# 7seg.net
KiCad netlist of a schematic drawn in Altium Designer
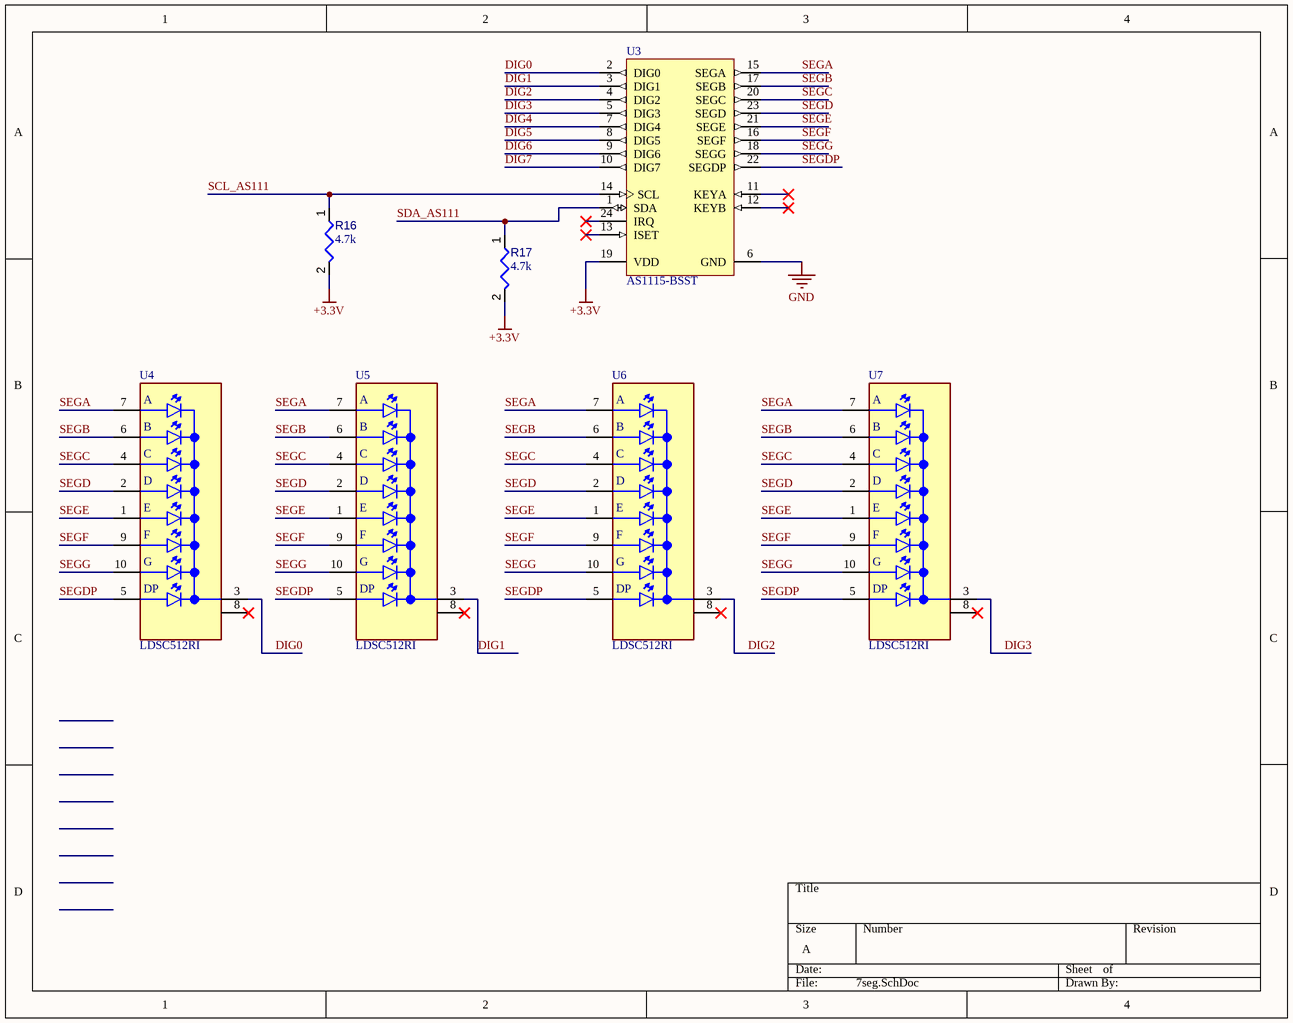
[diagram p0: 7seg.SchDoc]

(export (version "E")
  (design (tool "Eeschema 10.0.6"))
  (components
    (comp (ref "R16")
      (value "4.7k")
      (footprint "RESC0402(1005)_L")
      (description "Chip Resistor, 4,7 kOhms, +/-1 %, 63 mW, -55 to 155 degC, 0402")
      (fields (field (name "POWER") "63mW") (field (name "TOLERANCE") "1%"))
      (libsource (lib "Talha Khan") (part "RES-2"))
    )
    (comp (ref "R17")
      (value "4.7k")
      (footprint "RESC0402(1005)_L")
      (description "Chip Resistor, 4,7 kOhms, +/-1 %, 63 mW, -55 to 155 degC, 0402")
      (fields (field (name "POWER") "63mW") (field (name "TOLERANCE") "1%"))
      (libsource (lib "Talha Khan") (part "RES-2"))
    )
    (comp (ref "U3")
      (value "AS1115-BSST")
      (footprint "AMS-QSOP-24-8645X3900DE_N")
      (description "8Digits Tape & Reel (TR) 8x (7Segment) 64LED SERIAL display driver 350muA 5.5V 8.66mm -40C~85C")
      (libsource (lib "Talha Khan") (part "AMS-AS1115-QSOP-24"))
    )
    (comp (ref "U4")
      (value "LDSC512RI")
      (footprint "LED_LDSC512RI")
      (description ".56IN. 7 SEGMENT SINGLE DISPLAY, 565NM GREEN, GRAY FACE, WHITE SEGMENTS, COMMON")
      (fields (field (name "MF") "Lumex") (field (name "MP") "LDS-C512RI"))
      (libsource (lib "Talha Khan") (part "LDSC512RI"))
    )
    (comp (ref "U5")
      (value "LDSC512RI")
      (footprint "LED_LDSC512RI")
      (description ".56IN. 7 SEGMENT SINGLE DISPLAY, 565NM GREEN, GRAY FACE, WHITE SEGMENTS, COMMON")
      (fields (field (name "MF") "Lumex") (field (name "MP") "LDS-C512RI"))
      (libsource (lib "Talha Khan") (part "LDSC512RI"))
    )
    (comp (ref "U6")
      (value "LDSC512RI")
      (footprint "LED_LDSC512RI")
      (description ".56IN. 7 SEGMENT SINGLE DISPLAY, 565NM GREEN, GRAY FACE, WHITE SEGMENTS, COMMON")
      (fields (field (name "MF") "Lumex") (field (name "MP") "LDS-C512RI"))
      (libsource (lib "Talha Khan") (part "LDSC512RI"))
    )
    (comp (ref "U7")
      (value "LDSC512RI")
      (footprint "LED_LDSC512RI")
      (description ".56IN. 7 SEGMENT SINGLE DISPLAY, 565NM GREEN, GRAY FACE, WHITE SEGMENTS, COMMON")
      (fields (field (name "MF") "Lumex") (field (name "MP") "LDS-C512RI"))
      (libsource (lib "Talha Khan") (part "LDSC512RI"))
    )
  )
  (nets
    (net (code "1") (name "+3.3V") (class "Default")
      (node (ref "R16") (pin "2") (pinfunction "2_2") (pintype "passive"))
      (node (ref "R17") (pin "2") (pinfunction "2_2") (pintype "passive"))
      (node (ref "U3") (pin "19") (pinfunction "VDD_19") (pintype "power_in"))
    )
    (net (code "2") (name "/DIG0") (class "Default")
      (node (ref "U3") (pin "2") (pinfunction "DIG0_2") (pintype "output"))
      (node (ref "U4") (pin "3") (pinfunction "CC_3") (pintype "passive"))
    )
    (net (code "3") (name "/DIG1") (class "Default")
      (node (ref "U3") (pin "3") (pinfunction "DIG1_3") (pintype "output"))
      (node (ref "U5") (pin "3") (pinfunction "CC_3") (pintype "passive"))
    )
    (net (code "4") (name "/DIG2") (class "Default")
      (node (ref "U3") (pin "4") (pinfunction "DIG2_4") (pintype "output"))
      (node (ref "U6") (pin "3") (pinfunction "CC_3") (pintype "passive"))
    )
    (net (code "5") (name "/DIG3") (class "Default")
      (node (ref "U3") (pin "5") (pinfunction "DIG3_5") (pintype "output"))
      (node (ref "U7") (pin "3") (pinfunction "CC_3") (pintype "passive"))
    )
    (net (code "6") (name "/DIG4") (class "Default")
      (node (ref "U3") (pin "7") (pinfunction "DIG4_7") (pintype "output"))
    )
    (net (code "7") (name "/DIG5") (class "Default")
      (node (ref "U3") (pin "8") (pinfunction "DIG5_8") (pintype "output"))
    )
    (net (code "8") (name "/DIG6") (class "Default")
      (node (ref "U3") (pin "9") (pinfunction "DIG6_9") (pintype "output"))
    )
    (net (code "9") (name "/DIG7") (class "Default")
      (node (ref "U3") (pin "10") (pinfunction "DIG7_10") (pintype "output"))
    )
    (net (code "10") (name "/SCL_AS111") (class "Default")
      (node (ref "R16") (pin "1") (pinfunction "1_1") (pintype "passive"))
      (node (ref "U3") (pin "14") (pinfunction "SCL_14") (pintype "input"))
    )
    (net (code "11") (name "/SDA_AS111") (class "Default")
      (node (ref "R17") (pin "1") (pinfunction "1_1") (pintype "passive"))
      (node (ref "U3") (pin "1") (pinfunction "SDA_1") (pintype "bidirectional"))
    )
    (net (code "12") (name "/SEGA") (class "Default")
      (node (ref "U3") (pin "15") (pinfunction "SEGA_15") (pintype "output"))
      (node (ref "U4") (pin "7") (pinfunction "A_7") (pintype "passive"))
      (node (ref "U5") (pin "7") (pinfunction "A_7") (pintype "passive"))
      (node (ref "U6") (pin "7") (pinfunction "A_7") (pintype "passive"))
      (node (ref "U7") (pin "7") (pinfunction "A_7") (pintype "passive"))
    )
    (net (code "13") (name "/SEGB") (class "Default")
      (node (ref "U3") (pin "17") (pinfunction "SEGB_17") (pintype "output"))
      (node (ref "U4") (pin "6") (pinfunction "B_6") (pintype "passive"))
      (node (ref "U5") (pin "6") (pinfunction "B_6") (pintype "passive"))
      (node (ref "U6") (pin "6") (pinfunction "B_6") (pintype "passive"))
      (node (ref "U7") (pin "6") (pinfunction "B_6") (pintype "passive"))
    )
    (net (code "14") (name "/SEGC") (class "Default")
      (node (ref "U3") (pin "20") (pinfunction "SEGC_20") (pintype "output"))
      (node (ref "U4") (pin "4") (pinfunction "C_4") (pintype "passive"))
      (node (ref "U5") (pin "4") (pinfunction "C_4") (pintype "passive"))
      (node (ref "U6") (pin "4") (pinfunction "C_4") (pintype "passive"))
      (node (ref "U7") (pin "4") (pinfunction "C_4") (pintype "passive"))
    )
    (net (code "15") (name "/SEGD") (class "Default")
      (node (ref "U3") (pin "23") (pinfunction "SEGD_23") (pintype "output"))
      (node (ref "U4") (pin "2") (pinfunction "D_2") (pintype "passive"))
      (node (ref "U5") (pin "2") (pinfunction "D_2") (pintype "passive"))
      (node (ref "U6") (pin "2") (pinfunction "D_2") (pintype "passive"))
      (node (ref "U7") (pin "2") (pinfunction "D_2") (pintype "passive"))
    )
    (net (code "16") (name "/SEGDP") (class "Default")
      (node (ref "U3") (pin "22") (pinfunction "SEGDP_22") (pintype "output"))
      (node (ref "U4") (pin "5") (pinfunction "DP_5") (pintype "passive"))
      (node (ref "U5") (pin "5") (pinfunction "DP_5") (pintype "passive"))
      (node (ref "U6") (pin "5") (pinfunction "DP_5") (pintype "passive"))
      (node (ref "U7") (pin "5") (pinfunction "DP_5") (pintype "passive"))
    )
    (net (code "17") (name "/SEGE") (class "Default")
      (node (ref "U3") (pin "21") (pinfunction "SEGE_21") (pintype "output"))
      (node (ref "U4") (pin "1") (pinfunction "E_1") (pintype "passive"))
      (node (ref "U5") (pin "1") (pinfunction "E_1") (pintype "passive"))
      (node (ref "U6") (pin "1") (pinfunction "E_1") (pintype "passive"))
      (node (ref "U7") (pin "1") (pinfunction "E_1") (pintype "passive"))
    )
    (net (code "18") (name "/SEGF") (class "Default")
      (node (ref "U3") (pin "16") (pinfunction "SEGF_16") (pintype "output"))
      (node (ref "U4") (pin "9") (pinfunction "F_9") (pintype "passive"))
      (node (ref "U5") (pin "9") (pinfunction "F_9") (pintype "passive"))
      (node (ref "U6") (pin "9") (pinfunction "F_9") (pintype "passive"))
      (node (ref "U7") (pin "9") (pinfunction "F_9") (pintype "passive"))
    )
    (net (code "19") (name "/SEGG") (class "Default")
      (node (ref "U3") (pin "18") (pinfunction "SEGG_18") (pintype "output"))
      (node (ref "U4") (pin "10") (pinfunction "G_10") (pintype "passive"))
      (node (ref "U5") (pin "10") (pinfunction "G_10") (pintype "passive"))
      (node (ref "U6") (pin "10") (pinfunction "G_10") (pintype "passive"))
      (node (ref "U7") (pin "10") (pinfunction "G_10") (pintype "passive"))
    )
    (net (code "20") (name "GND") (class "Default")
      (node (ref "U3") (pin "6") (pinfunction "GND_6") (pintype "power_in"))
    )
    (net (code "21") (name "unconnected-(U3-IRQ-Pad24)") (class "Default")
      (node (ref "U3") (pin "24") (pinfunction "IRQ_24") (pintype "tri_state+no_connect"))
    )
    (net (code "22") (name "unconnected-(U3-ISET-Pad13)") (class "Default")
      (node (ref "U3") (pin "13") (pinfunction "ISET_13") (pintype "input+no_connect"))
    )
    (net (code "23") (name "unconnected-(U3-KEYA-Pad11)") (class "Default")
      (node (ref "U3") (pin "11") (pinfunction "KEYA_11") (pintype "input+no_connect"))
    )
    (net (code "24") (name "unconnected-(U3-KEYB-Pad12)") (class "Default")
      (node (ref "U3") (pin "12") (pinfunction "KEYB_12") (pintype "input+no_connect"))
    )
    (net (code "25") (name "unconnected-(U4-CC-Pad8)") (class "Default")
      (node (ref "U4") (pin "8") (pinfunction "CC_8") (pintype "passive+no_connect"))
    )
    (net (code "26") (name "unconnected-(U5-CC-Pad8)") (class "Default")
      (node (ref "U5") (pin "8") (pinfunction "CC_8") (pintype "passive+no_connect"))
    )
    (net (code "27") (name "unconnected-(U6-CC-Pad8)") (class "Default")
      (node (ref "U6") (pin "8") (pinfunction "CC_8") (pintype "passive+no_connect"))
    )
    (net (code "28") (name "unconnected-(U7-CC-Pad8)") (class "Default")
      (node (ref "U7") (pin "8") (pinfunction "CC_8") (pintype "passive+no_connect"))
    )
  )
)
